# STorM32_NT_imu_v10_mini-mpu6000.net
KiCad netlist of a schematic drawn in EAGLE
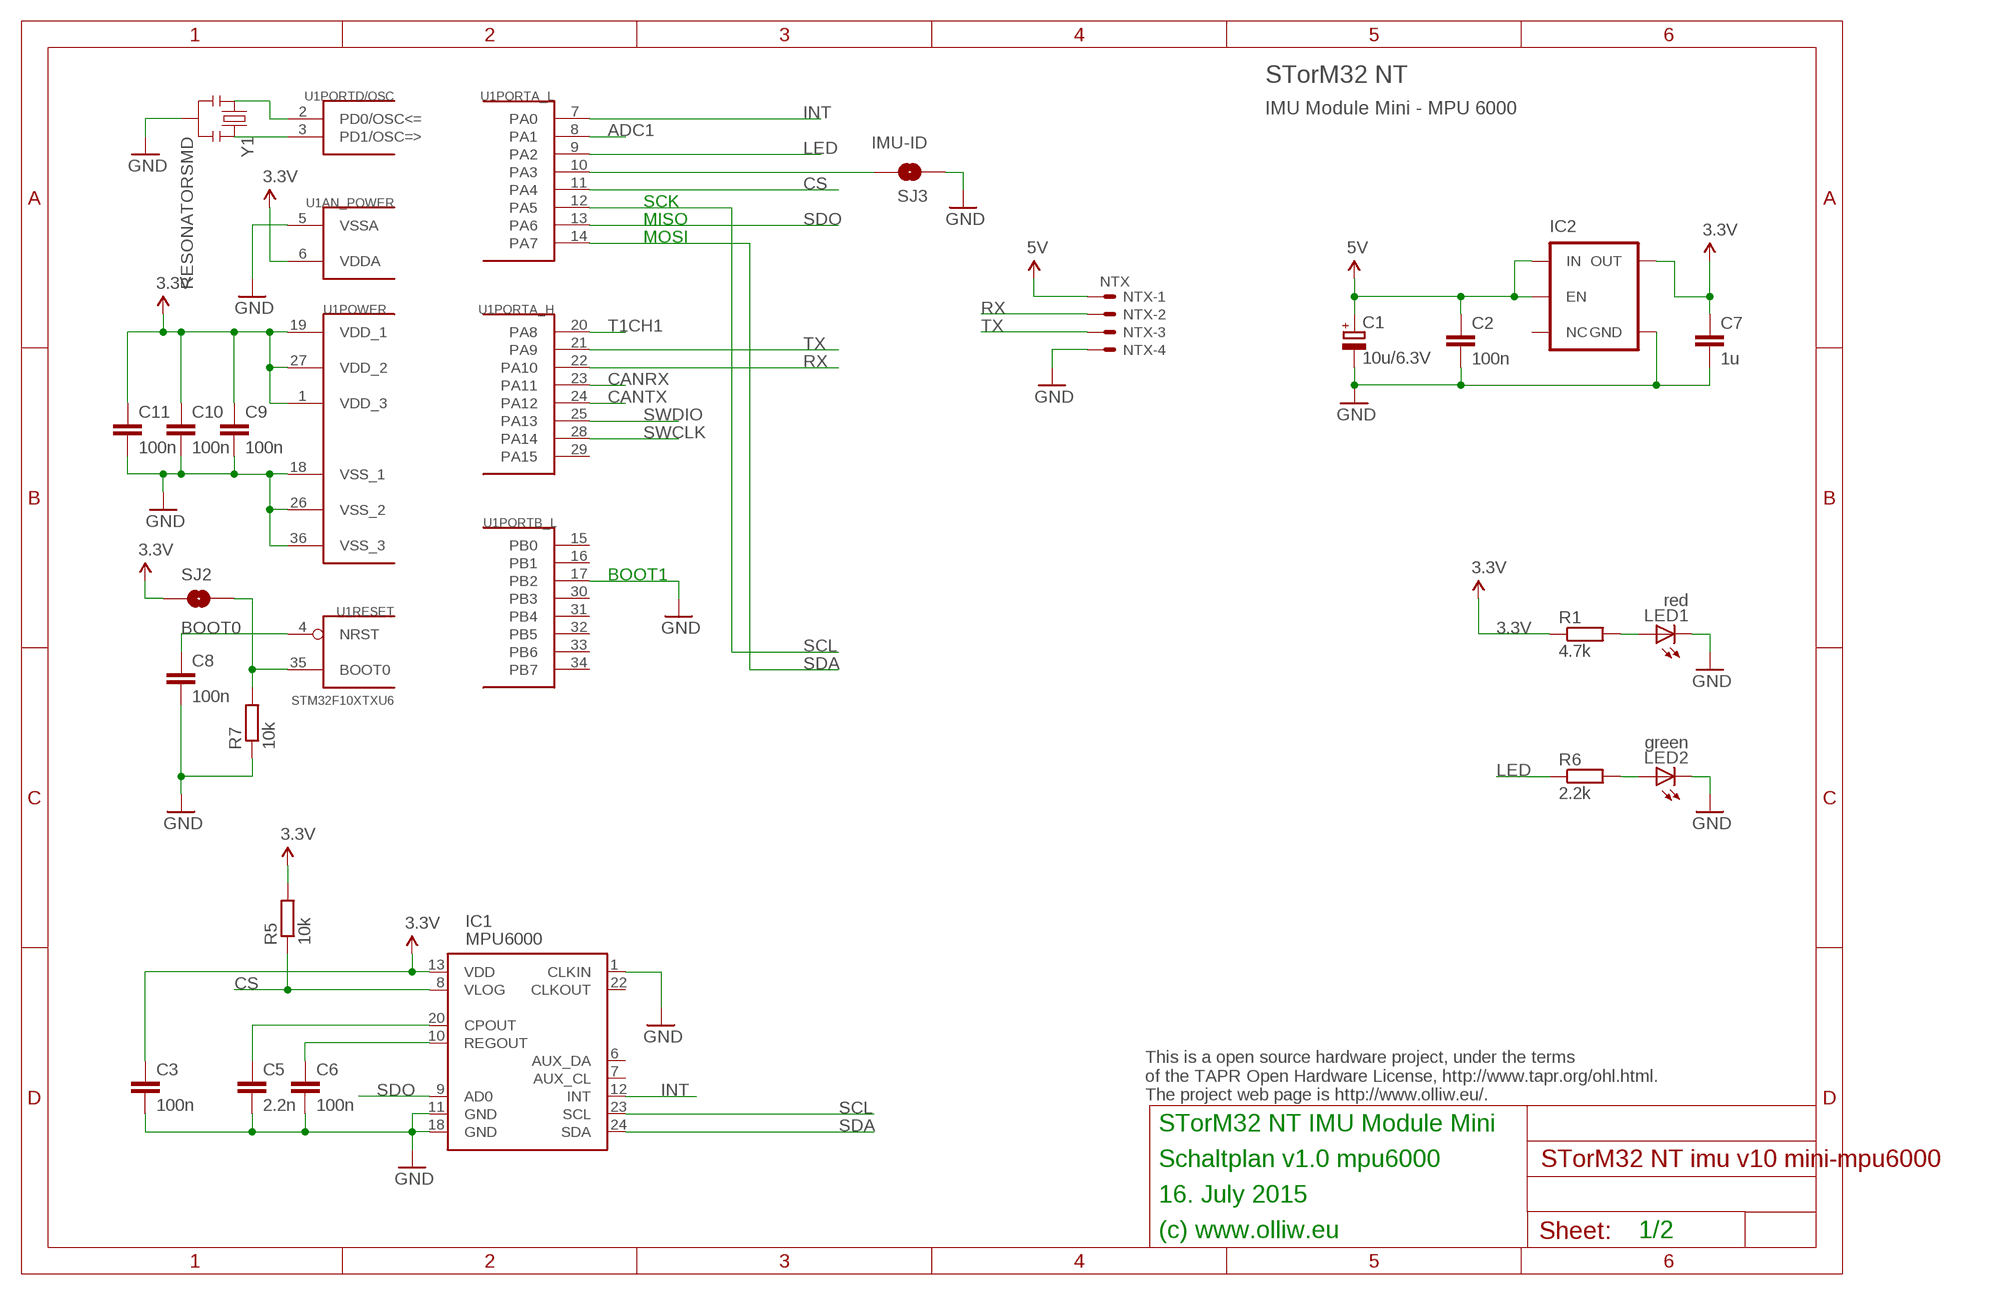
[diagram p0: schematic, sheet 1]

(export (version "E")
  (design (tool "Eeschema 10.0.6"))
  (components
    (comp (ref "C1")
      (value "10u/6.3V")
      (footprint "eagle-import:SMC_A")
      (libsource (lib "eagle-import") (part "CPOL-EUSMCA"))
    )
    (comp (ref "C2")
      (value "100n")
      (footprint "eagle-import:C0402")
      (libsource (lib "eagle-import") (part "C-EUC0402"))
    )
    (comp (ref "C3")
      (value "100n")
      (footprint "eagle-import:C0402")
      (libsource (lib "eagle-import") (part "C-EUC0402"))
    )
    (comp (ref "C5")
      (value "2.2n")
      (footprint "eagle-import:C0402")
      (libsource (lib "eagle-import") (part "C-EUC0402"))
    )
    (comp (ref "C6")
      (value "100n")
      (footprint "eagle-import:C0402")
      (libsource (lib "eagle-import") (part "C-EUC0402"))
    )
    (comp (ref "C7")
      (value "1u")
      (footprint "eagle-import:C0402")
      (libsource (lib "eagle-import") (part "C-EUC0402"))
    )
    (comp (ref "C8")
      (value "100n")
      (footprint "eagle-import:C0402")
      (libsource (lib "eagle-import") (part "C-EUC0402"))
    )
    (comp (ref "C9")
      (value "100n")
      (footprint "eagle-import:C0402")
      (libsource (lib "eagle-import") (part "C-EUC0402"))
    )
    (comp (ref "C10")
      (value "100n")
      (footprint "eagle-import:C0402")
      (libsource (lib "eagle-import") (part "C-EUC0402"))
    )
    (comp (ref "C11")
      (value "100n")
      (footprint "eagle-import:C0402")
      (libsource (lib "eagle-import") (part "C-EUC0402"))
    )
    (comp (ref "IC1")
      (value "MPU6000")
      (footprint "eagle-import:QFN-24")
      (libsource (lib "eagle-import") (part "IMU3000"))
    )
    (comp (ref "IC2")
      (value "V_REG_TPS76433SOT23-5")
      (footprint "eagle-import:SOT23-5")
      (libsource (lib "eagle-import") (part "V_REG_TPS76433SOT23-5"))
    )
    (comp (ref "LED1")
      (value "red")
      (footprint "eagle-import:CHIPLED_0603")
      (libsource (lib "eagle-import") (part "LEDCHIPLED_0603"))
    )
    (comp (ref "LED2")
      (value "green")
      (footprint "eagle-import:CHIPLED_0603")
      (libsource (lib "eagle-import") (part "LEDCHIPLED_0603"))
    )
    (comp (ref "NTX")
      (value "NTX")
      (footprint "eagle-import:SM04B-SRSS-TB")
      (libsource (lib "eagle-import") (part "?M04B-SRSS-TBS"))
    )
    (comp (ref "R1")
      (value "4.7k")
      (footprint "eagle-import:R0402")
      (libsource (lib "eagle-import") (part "R-EU_R0402"))
    )
    (comp (ref "R5")
      (value "10k")
      (footprint "eagle-import:R0402")
      (libsource (lib "eagle-import") (part "R-EU_R0402"))
    )
    (comp (ref "R6")
      (value "2.2k")
      (footprint "eagle-import:R0402")
      (libsource (lib "eagle-import") (part "R-EU_R0402"))
    )
    (comp (ref "R7")
      (value "10k")
      (footprint "eagle-import:R0402")
      (libsource (lib "eagle-import") (part "R-EU_R0402"))
    )
    (comp (ref "SJ2")
      (value "BOOT0")
      (footprint "eagle-import:SJ_2S-NO")
      (libsource (lib "eagle-import") (part "SOLDERJUMPERNO"))
    )
    (comp (ref "SJ3")
      (value "IMU-ID")
      (footprint "eagle-import:SJ_2S-NO")
      (libsource (lib "eagle-import") (part "SOLDERJUMPERNO"))
    )
    (comp (ref "U1")
      (value "STM32F10XTXU6")
      (footprint "eagle-import:VFQFPN36")
      (libsource (lib "eagle-import") (part "STM32F10XTXU6"))
    )
    (comp (ref "Y1")
      (value "RESONATORSMD")
      (footprint "eagle-import:RESONATOR-SMD")
      (libsource (lib "eagle-import") (part "RESONATORSMD"))
    )
  )
  (nets
    (net (code "1") (name "/ADC1") (class "Default")
      (node (ref "U1") (pin "8") (pinfunction "PA1_8") (pintype "bidirectional"))
    )
    (net (code "2") (name "/CANRX") (class "Default")
      (node (ref "U1") (pin "23") (pinfunction "PA11_23") (pintype "bidirectional"))
    )
    (net (code "3") (name "/CANTX") (class "Default")
      (node (ref "U1") (pin "24") (pinfunction "PA12_24") (pintype "bidirectional"))
    )
    (net (code "4") (name "/CS") (class "Default")
      (node (ref "IC1") (pin "8") (pinfunction "VLOG_8") (pintype "bidirectional"))
      (node (ref "R5") (pin "1") (pinfunction "1_1") (pintype "passive"))
      (node (ref "U1") (pin "11") (pinfunction "PA4_11") (pintype "bidirectional"))
    )
    (net (code "5") (name "/INT") (class "Default")
      (node (ref "IC1") (pin "12") (pinfunction "INT_12") (pintype "bidirectional"))
      (node (ref "U1") (pin "7") (pinfunction "PA0_7") (pintype "bidirectional"))
    )
    (net (code "6") (name "/LED") (class "Default")
      (node (ref "R6") (pin "1") (pinfunction "1_1") (pintype "passive"))
      (node (ref "U1") (pin "9") (pinfunction "PA2_9") (pintype "bidirectional"))
    )
    (net (code "7") (name "/RX") (class "Default")
      (node (ref "NTX") (pin "2") (pinfunction "S_2") (pintype "passive"))
      (node (ref "U1") (pin "22") (pinfunction "PA10_22") (pintype "bidirectional"))
    )
    (net (code "8") (name "/SCL") (class "Default")
      (node (ref "IC1") (pin "23") (pinfunction "SCL_23") (pintype "bidirectional"))
      (node (ref "U1") (pin "12") (pinfunction "PA5_12") (pintype "bidirectional"))
    )
    (net (code "9") (name "/SDA") (class "Default")
      (node (ref "IC1") (pin "24") (pinfunction "SDA_24") (pintype "bidirectional"))
      (node (ref "U1") (pin "14") (pinfunction "PA7_14") (pintype "bidirectional"))
    )
    (net (code "10") (name "/SDO") (class "Default")
      (node (ref "IC1") (pin "9") (pinfunction "AD0_9") (pintype "bidirectional"))
      (node (ref "U1") (pin "13") (pinfunction "PA6_13") (pintype "bidirectional"))
    )
    (net (code "11") (name "/SWCLK") (class "Default")
      (node (ref "U1") (pin "28") (pinfunction "PA14_28") (pintype "bidirectional"))
    )
    (net (code "12") (name "/SWDIO") (class "Default")
      (node (ref "U1") (pin "25") (pinfunction "PA13_25") (pintype "bidirectional"))
    )
    (net (code "13") (name "/T1CH1") (class "Default")
      (node (ref "U1") (pin "20") (pinfunction "PA8_20") (pintype "bidirectional"))
    )
    (net (code "14") (name "/TX") (class "Default")
      (node (ref "NTX") (pin "3") (pinfunction "S_3") (pintype "passive"))
      (node (ref "U1") (pin "21") (pinfunction "PA9_21") (pintype "bidirectional"))
    )
    (net (code "15") (name "3.3V") (class "Default")
      (node (ref "C10") (pin "1") (pinfunction "1_1") (pintype "passive"))
      (node (ref "C11") (pin "1") (pinfunction "1_1") (pintype "passive"))
      (node (ref "C3") (pin "1") (pinfunction "1_1") (pintype "passive"))
      (node (ref "C7") (pin "1") (pinfunction "1_1") (pintype "passive"))
      (node (ref "C9") (pin "1") (pinfunction "1_1") (pintype "passive"))
      (node (ref "IC1") (pin "13") (pinfunction "VDD_13") (pintype "bidirectional"))
      (node (ref "IC2") (pin "5") (pinfunction "OUT_5") (pintype "passive"))
      (node (ref "R1") (pin "1") (pinfunction "1_1") (pintype "passive"))
      (node (ref "R5") (pin "2") (pinfunction "2_2") (pintype "passive"))
      (node (ref "SJ2") (pin "1") (pinfunction "1_1") (pintype "passive"))
      (node (ref "U1") (pin "1") (pinfunction "VDD_3_1") (pintype "power_in"))
      (node (ref "U1") (pin "19") (pinfunction "VDD_1_19") (pintype "power_in"))
      (node (ref "U1") (pin "27") (pinfunction "VDD_2_27") (pintype "power_in"))
      (node (ref "U1") (pin "6") (pinfunction "VDDA_6") (pintype "power_in"))
    )
    (net (code "16") (name "5V") (class "Default")
      (node (ref "C1") (pin "+") (pinfunction "+_+") (pintype "passive"))
      (node (ref "C2") (pin "1") (pinfunction "1_1") (pintype "passive"))
      (node (ref "IC2") (pin "1") (pinfunction "IN_1") (pintype "input"))
      (node (ref "IC2") (pin "3") (pinfunction "EN_3") (pintype "input"))
      (node (ref "NTX") (pin "1") (pinfunction "S_1") (pintype "passive"))
    )
    (net (code "17") (name "GND") (class "Default")
      (node (ref "C1") (pin "-") (pinfunction "-_-") (pintype "passive"))
      (node (ref "C10") (pin "2") (pinfunction "2_2") (pintype "passive"))
      (node (ref "C11") (pin "2") (pinfunction "2_2") (pintype "passive"))
      (node (ref "C2") (pin "2") (pinfunction "2_2") (pintype "passive"))
      (node (ref "C3") (pin "2") (pinfunction "2_2") (pintype "passive"))
      (node (ref "C5") (pin "2") (pinfunction "2_2") (pintype "passive"))
      (node (ref "C6") (pin "2") (pinfunction "2_2") (pintype "passive"))
      (node (ref "C7") (pin "2") (pinfunction "2_2") (pintype "passive"))
      (node (ref "C8") (pin "2") (pinfunction "2_2") (pintype "passive"))
      (node (ref "C9") (pin "2") (pinfunction "2_2") (pintype "passive"))
      (node (ref "IC1") (pin "1") (pinfunction "CLKIN_1") (pintype "bidirectional"))
      (node (ref "IC1") (pin "11") (pinfunction "GND_11") (pintype "bidirectional"))
      (node (ref "IC1") (pin "18") (pinfunction "GND_18") (pintype "bidirectional"))
      (node (ref "IC2") (pin "2") (pinfunction "GND_2") (pintype "input"))
      (node (ref "LED1") (pin "C") (pinfunction "C_C") (pintype "passive"))
      (node (ref "LED2") (pin "C") (pinfunction "C_C") (pintype "passive"))
      (node (ref "NTX") (pin "4") (pinfunction "S_4") (pintype "passive"))
      (node (ref "R7") (pin "1") (pinfunction "1_1") (pintype "passive"))
      (node (ref "SJ3") (pin "1") (pinfunction "1_1") (pintype "passive"))
      (node (ref "U1") (pin "17") (pinfunction "PB2_17") (pintype "bidirectional"))
      (node (ref "U1") (pin "18") (pinfunction "VSS_1_18") (pintype "power_in"))
      (node (ref "U1") (pin "26") (pinfunction "VSS_2_26") (pintype "power_in"))
      (node (ref "U1") (pin "36") (pinfunction "VSS_3_36") (pintype "power_in"))
      (node (ref "U1") (pin "5") (pinfunction "VSSA_5") (pintype "power_in"))
      (node (ref "Y1") (pin "2") (pinfunction "2_2") (pintype "passive"))
    )
    (net (code "18") (name "Net-(IC1-CPOUT)") (class "Default")
      (node (ref "C5") (pin "1") (pinfunction "1_1") (pintype "passive"))
      (node (ref "IC1") (pin "20") (pinfunction "CPOUT_20") (pintype "bidirectional"))
    )
    (net (code "19") (name "Net-(IC1-REGOUT)") (class "Default")
      (node (ref "C6") (pin "1") (pinfunction "1_1") (pintype "passive"))
      (node (ref "IC1") (pin "10") (pinfunction "REGOUT_10") (pintype "bidirectional"))
    )
    (net (code "20") (name "Net-(LED1-PadA)") (class "Default")
      (node (ref "LED1") (pin "A") (pinfunction "A_A") (pintype "passive"))
      (node (ref "R1") (pin "2") (pinfunction "2_2") (pintype "passive"))
    )
    (net (code "21") (name "Net-(LED2-PadA)") (class "Default")
      (node (ref "LED2") (pin "A") (pinfunction "A_A") (pintype "passive"))
      (node (ref "R6") (pin "2") (pinfunction "2_2") (pintype "passive"))
    )
    (net (code "22") (name "Net-(U1C-PA3)") (class "Default")
      (node (ref "SJ3") (pin "2") (pinfunction "2_2") (pintype "passive"))
      (node (ref "U1") (pin "10") (pinfunction "PA3_10") (pintype "bidirectional"))
    )
    (net (code "23") (name "Net-(U1E-PD0{slash}OSC<=)") (class "Default")
      (node (ref "U1") (pin "2") (pinfunction "PD0/OSC<=_2") (pintype "bidirectional"))
      (node (ref "Y1") (pin "1") (pinfunction "1_1") (pintype "passive"))
    )
    (net (code "24") (name "Net-(U1E-PD1{slash}OSC=>)") (class "Default")
      (node (ref "U1") (pin "3") (pinfunction "PD1/OSC=>_3") (pintype "bidirectional"))
      (node (ref "Y1") (pin "3") (pinfunction "3_3") (pintype "passive"))
    )
    (net (code "25") (name "Net-(U1G-BOOT0)") (class "Default")
      (node (ref "R7") (pin "2") (pinfunction "2_2") (pintype "passive"))
      (node (ref "SJ2") (pin "2") (pinfunction "2_2") (pintype "passive"))
      (node (ref "U1") (pin "35") (pinfunction "BOOT0_35") (pintype "input"))
    )
    (net (code "26") (name "Net-(U1G-NRST)") (class "Default")
      (node (ref "C8") (pin "1") (pinfunction "1_1") (pintype "passive"))
      (node (ref "U1") (pin "4") (pinfunction "NRST_4") (pintype "input"))
    )
    (net (code "27") (name "unconnected-(IC1-AUX_CL-Pad7)") (class "Default")
      (node (ref "IC1") (pin "7") (pinfunction "AUX_CL_7") (pintype "bidirectional"))
    )
    (net (code "28") (name "unconnected-(IC1-AUX_DA-Pad6)") (class "Default")
      (node (ref "IC1") (pin "6") (pinfunction "AUX_DA_6") (pintype "bidirectional"))
    )
    (net (code "29") (name "unconnected-(IC1-CLKOUT-Pad22)") (class "Default")
      (node (ref "IC1") (pin "22") (pinfunction "CLKOUT_22") (pintype "bidirectional"))
    )
    (net (code "30") (name "unconnected-(IC2-NC-Pad4)") (class "Default")
      (node (ref "IC2") (pin "4") (pinfunction "NC_4") (pintype "input"))
    )
    (net (code "31") (name "unconnected-(U1B-PA15-Pad29)") (class "Default")
      (node (ref "U1") (pin "29") (pinfunction "PA15_29") (pintype "bidirectional"))
    )
    (net (code "32") (name "unconnected-(U1D-PB0-Pad15)") (class "Default")
      (node (ref "U1") (pin "15") (pinfunction "PB0_15") (pintype "bidirectional"))
    )
    (net (code "33") (name "unconnected-(U1D-PB1-Pad16)") (class "Default")
      (node (ref "U1") (pin "16") (pinfunction "PB1_16") (pintype "bidirectional"))
    )
    (net (code "34") (name "unconnected-(U1D-PB3-Pad30)") (class "Default")
      (node (ref "U1") (pin "30") (pinfunction "PB3_30") (pintype "bidirectional"))
    )
    (net (code "35") (name "unconnected-(U1D-PB4-Pad31)") (class "Default")
      (node (ref "U1") (pin "31") (pinfunction "PB4_31") (pintype "bidirectional"))
    )
    (net (code "36") (name "unconnected-(U1D-PB5-Pad32)") (class "Default")
      (node (ref "U1") (pin "32") (pinfunction "PB5_32") (pintype "bidirectional"))
    )
    (net (code "37") (name "unconnected-(U1D-PB6-Pad33)") (class "Default")
      (node (ref "U1") (pin "33") (pinfunction "PB6_33") (pintype "bidirectional"))
    )
    (net (code "38") (name "unconnected-(U1D-PB7-Pad34)") (class "Default")
      (node (ref "U1") (pin "34") (pinfunction "PB7_34") (pintype "bidirectional"))
    )
  )
)
